# JTAG-USB-POWER.net
KiCad netlist of a schematic drawn in Altium Designer
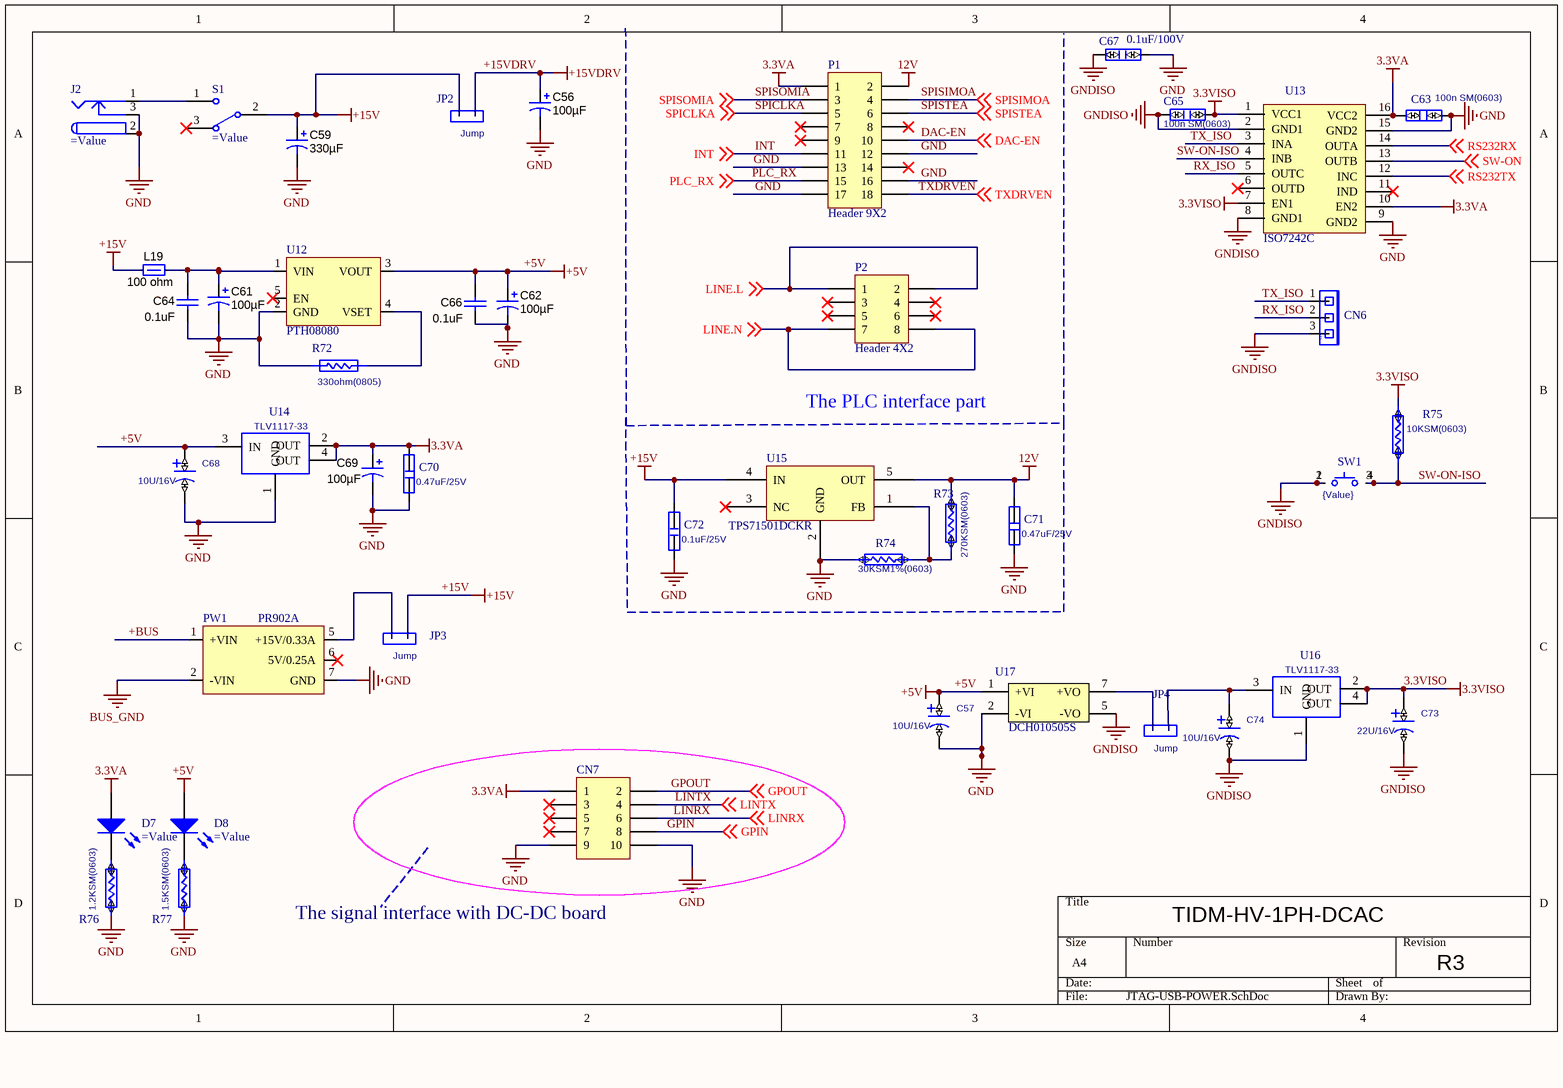
[diagram p0: JTAG-USB-POWER.SchDoc]

(export (version "E")
  (design (tool "Eeschema 10.0.6"))
  (components
    (comp (ref "C56")
      (value "EMVA500ADA101MHA0G")
      (footprint "CAPSMT_62_HA0")
      (description "CAP, AL, 100uF, 50V, +/-20%,  ohm, SMD")
      (fields
        (field (name "VALUEDISPLAYED") "100µF")
        (field (name "MANUFACTURER") "Nippon Chemi-Con")
        (field (name "PUBLISHER") "Texas Instruments")
      )
      (libsource (lib "Capacitor_Aluminum") (part "EMVA500ADA101MHA0G"))
    )
    (comp (ref "C57")
      (value "10U/16V")
      (footprint "CAP-3528")
      (description "CE5080R")
      (libsource (lib "AD-DIPWIN") (part "CE5080R"))
    )
    (comp (ref "C59")
      (value "2R5SVPE330M")
      (footprint "CAPSMT_62_HA0")
      (description "CAP, AL, 330uF, 2.5V, +/-20%, 0.015 ohm, SMD")
      (fields
        (field (name "MANUFACTURER") "Sanyo")
        (field (name "VALUEDISPLAYED") "330µF")
        (field (name "PUBLISHER") "Texas Instruments")
      )
      (libsource (lib "Pass12") (part "2R5SVPE330M"))
    )
    (comp (ref "C61")
      (value "EMVA500ADA101MHA0G")
      (footprint "CAPSMT_62_HA0")
      (description "CAP, AL, 100uF, 50V, +/-20%,  ohm, SMD")
      (fields
        (field (name "VALUEDISPLAYED") "100µF")
        (field (name "MANUFACTURER") "Nippon Chemi-Con")
        (field (name "PUBLISHER") "Texas Instruments")
      )
      (libsource (lib "Capacitor_Aluminum") (part "EMVA500ADA101MHA0G"))
    )
    (comp (ref "C62")
      (value "EMVA500ADA101MHA0G")
      (footprint "CAPSMT_62_HA0")
      (description "CAP, AL, 100uF, 50V, +/-20%,  ohm, SMD")
      (fields
        (field (name "VALUEDISPLAYED") "100µF")
        (field (name "MANUFACTURER") "Nippon Chemi-Con")
        (field (name "PUBLISHER") "Texas Instruments")
      )
      (libsource (lib "Capacitor_Aluminum") (part "EMVA500ADA101MHA0G"))
    )
    (comp (ref "C63")
      (value "100n SM(0603)")
      (footprint "C0603SM")
      (description "C0603SM")
      (libsource (lib "AD-SMDWIN") (part "C0603SM"))
    )
    (comp (ref "C64")
      (value "0.1uF")
      (footprint "0805")
      (description "CAP, CERM, xxxF, xxV, [TempCo], xx%, [PackageReference]")
      (fields
        (field (name "MANUFACTURER") "Used in BOM report")
        (field (name "PUBLISHER") "Texas Instruments")
      )
      (libsource (lib "MiscParts") (part "Capacitor"))
    )
    (comp (ref "C65")
      (value "100n SM(0603)")
      (footprint "C0603SM")
      (description "C0603SM")
      (libsource (lib "AD-SMDWIN") (part "C0603SM"))
    )
    (comp (ref "C66")
      (value "0.1uF")
      (footprint "0805")
      (description "CAP, CERM, xxxF, xxV, [TempCo], xx%, [PackageReference]")
      (fields
        (field (name "MANUFACTURER") "Used in BOM report")
        (field (name "PUBLISHER") "Texas Instruments")
      )
      (libsource (lib "MiscParts") (part "Capacitor"))
    )
    (comp (ref "C67")
      (value "0.1uF/100V")
      (footprint "C/7.5/3/7.5/R3")
      (description "C0603SM")
      (libsource (lib "AD-SMDWIN") (part "C0603SM"))
    )
    (comp (ref "C68")
      (value "10U/16V")
      (footprint "CAP-3528")
      (description "CE5080R")
      (libsource (lib "AD-DIPWIN") (part "CE5080R"))
    )
    (comp (ref "C69")
      (value "EMVA500ADA101MHA0G")
      (footprint "CAPSMT_62_HA0")
      (description "CAP, AL, 100uF, 50V, +/-20%,  ohm, SMD")
      (fields
        (field (name "VALUEDISPLAYED") "100µF")
        (field (name "MANUFACTURER") "Nippon Chemi-Con")
        (field (name "PUBLISHER") "Texas Instruments")
      )
      (libsource (lib "Capacitor_Aluminum") (part "EMVA500ADA101MHA0G"))
    )
    (comp (ref "C70")
      (value "0.47uF/25V")
      (footprint "C0603SM")
      (description "C0805BSM")
      (libsource (lib "AD-SMDWIN") (part "C0805BSM"))
    )
    (comp (ref "C71")
      (value "0.47uF/25V")
      (footprint "C0603SM")
      (description "C0805BSM")
      (libsource (lib "AD-SMDWIN") (part "C0805BSM"))
    )
    (comp (ref "C72")
      (value "0.1uF/25V")
      (footprint "C0603SM")
      (description "C0805BSM")
      (libsource (lib "AD-SMDWIN") (part "C0805BSM"))
    )
    (comp (ref "C73")
      (value "22U/16V")
      (footprint "CAP-3528")
      (description "CE5080R")
      (libsource (lib "AD-DIPWIN") (part "CE5080R"))
    )
    (comp (ref "C74")
      (value "10U/16V")
      (footprint "CAP-3528")
      (description "CE5080R")
      (libsource (lib "AD-DIPWIN") (part "CE5080R"))
    )
    (comp (ref "CN6")
      (value "SCI_PORT")
      (footprint "HDR1X3")
      (description "DB01P03")
      (libsource (lib "AD-DIPWIN") (part "DB01P03"))
    )
    (comp (ref "CN7")
      (value "~")
      (footprint "HDR2X5")
      (description "Header, 5-Pin, Dual row")
      (fields (field (name "PUBLISHER") "Altium Limited"))
      (libsource (lib "Miscellaneous Connectors") (part "Header 5X2"))
    )
    (comp (ref "D7")
      (value "~")
      (footprint "LED0805")
      (description "Typical INFRARED GaAs LED")
      (fields (field (name "PUBLISHER") "Altium Limited"))
      (libsource (lib "Miscellaneous Devices") (part "LED0"))
    )
    (comp (ref "D8")
      (value "~")
      (footprint "LED0805")
      (description "Typical INFRARED GaAs LED")
      (fields (field (name "PUBLISHER") "Altium Limited"))
      (libsource (lib "Miscellaneous Devices") (part "LED0"))
    )
    (comp (ref "J2")
      (value "~")
      (footprint "DCJACK")
      (description "Low Voltage Power Supply Connector")
      (fields (field (name "PUBLISHER") "Altium Limited"))
      (libsource (lib "Miscellaneous Connectors") (part "PWR2.5"))
    )
    (comp (ref "JP2")
      (value "Jump")
      (footprint "HDR1X2")
      (description "J7")
      (libsource (lib "AD-DIPWIN") (part "J7"))
    )
    (comp (ref "JP3")
      (value "Jump")
      (footprint "HDR1X2")
      (description "J7")
      (libsource (lib "AD-DIPWIN") (part "J7"))
    )
    (comp (ref "JP4")
      (value "Jump")
      (footprint "HDR1X2")
      (description "J7")
      (libsource (lib "AD-DIPWIN") (part "J7"))
    )
    (comp (ref "L19")
      (value "100 ohm")
      (footprint "1206")
      (description "Ferrite Bead, 100 ohm @ 100MHz, 3A, 1206")
      (fields
        (field (name "PARTNUMBER") "HI1206N101R-10")
        (field (name "MANUFACTURER") "Laird-Signal Integrity Products")
        (field (name "PUBLISHER") "Texas Instruments")
      )
      (libsource (lib "FerriteBead") (part "HI1206N101R-10"))
    )
    (comp (ref "P1")
      (value "Header 9X2")
      (footprint "HDR2X9")
      (description "Header, 9-Pin, Dual row")
      (fields (field (name "PUBLISHER") "Altium Limited"))
      (libsource (lib "Miscellaneous Connectors") (part "Header 9X2"))
    )
    (comp (ref "P2")
      (value "Header 4X2")
      (footprint "HDR2X4")
      (description "Header, 4-Pin, Dual row")
      (fields (field (name "PUBLISHER") "Altium Limited"))
      (libsource (lib "Miscellaneous Connectors") (part "Header 4X2"))
    )
    (comp (ref "PW1")
      (value "~")
      (footprint "PR902A")
      (fields (field (name "ALTIUM_UNNAMED_1") "PR902A"))
      (libsource (lib "Schlib1") (part "PR902A"))
    )
    (comp (ref "R72")
      (value "330ohm(0805)")
      (footprint "R0805BSM")
      (description "R0805BSM")
      (libsource (lib "AD-SMDWIN") (part "R0805BSM"))
    )
    (comp (ref "R73")
      (value "270KSM(0603)")
      (footprint "R0603SM")
      (description "R0603SM")
      (libsource (lib "AD-SMDWIN") (part "R0603SM"))
    )
    (comp (ref "R74")
      (value "30KSM1%(0603)")
      (footprint "R0603SM")
      (description "R0603SM")
      (libsource (lib "AD-SMDWIN") (part "R0603SM"))
    )
    (comp (ref "R75")
      (value "10KSM(0603)")
      (footprint "R0603SM")
      (description "R0603SM")
      (libsource (lib "AD-SMDWIN") (part "R0603SM"))
    )
    (comp (ref "R76")
      (value "1.2KSM(0603)")
      (footprint "R0603SM")
      (description "R0603SM")
      (libsource (lib "AD-SMDWIN") (part "R0603SM"))
    )
    (comp (ref "R77")
      (value "1.5KSM(0603)")
      (footprint "R0603SM")
      (description "R0603SM")
      (libsource (lib "AD-SMDWIN") (part "R0603SM"))
    )
    (comp (ref "S1")
      (value "~")
      (footprint "SW-3P8X5")
      (description "SPDT Subminiature Toggle Switch, Right Angle Mounting, Vertical Actuation")
      (fields (field (name "PUBLISHER") "Altium Limited"))
      (libsource (lib "Miscellaneous Devices") (part "SW-SPDT"))
    )
    (comp (ref "SW1")
      (value "{Value}")
      (footprint "KRS640")
      (description "KRS640")
      (libsource (lib "AD-DIPWIN") (part "KRS640"))
    )
    (comp (ref "U12")
      (value "~")
      (footprint "PTH08080")
      (fields (field (name "ALTIUM_UNNAMED_1") "PTH08080"))
      (libsource (lib "SOLAR") (part "Component_1"))
    )
    (comp (ref "U13")
      (value "~")
      (footprint "IC-SOIC16P-1.27DW")
      (description "ISO7242")
      (fields (field (name "ALTIUM_UNNAMED_1") "ISO7242C"))
      (libsource (lib "Rectifier_Board") (part "ISO7242"))
    )
    (comp (ref "U14")
      (value "TLV1117-33")
      (footprint "SOT-223-3P")
      (description "LM1117SM")
      (libsource (lib "SolarInv") (part "LM1117SM"))
    )
    (comp (ref "U15")
      (value "TPS71501DCKR")
      (footprint "SOT5-DCK(SC-70)")
      (fields (field (name "ALTIUM_UNNAMED_1") "TPS71501DCKR"))
      (libsource (lib "TPS715XX") (part "TPS71501DCKR"))
    )
    (comp (ref "U16")
      (value "TLV1117-33")
      (footprint "SOT-223-3P")
      (description "LM1117SM")
      (libsource (lib "SolarInv") (part "LM1117SM"))
    )
    (comp (ref "U17")
      (value "~")
      (footprint "DCH010505")
      (fields (field (name "ALTIUM_UNNAMED_1") "DCH010505S"))
      (libsource (lib "Rectifier_Board") (part "DCH010505S"))
    )
  )
  (nets
    (net (code "1") (name "+5V") (class "Default")
      (node (ref "C57") (pin "1") (pinfunction "1_1") (pintype "bidirectional"))
      (node (ref "C62") (pin "1") (pinfunction "+_1") (pintype "passive"))
      (node (ref "C66") (pin "1") (pinfunction "1_1") (pintype "passive"))
      (node (ref "C68") (pin "1") (pinfunction "1_1") (pintype "bidirectional"))
      (node (ref "D8") (pin "1") (pinfunction "A_1") (pintype "passive"))
      (node (ref "U12") (pin "3") (pinfunction "VOUT_3") (pintype "passive"))
      (node (ref "U14") (pin "3") (pinfunction "IN_3") (pintype "passive"))
      (node (ref "U17") (pin "1") (pinfunction "+VI_1") (pintype "open_emitter"))
    )
    (net (code "2") (name "+15V") (class "Default")
      (node (ref "C59") (pin "1") (pinfunction "+_1") (pintype "passive"))
      (node (ref "C72") (pin "2") (pinfunction "2_2") (pintype "passive"))
      (node (ref "JP2") (pin "1") (pinfunction "1_1") (pintype "bidirectional"))
      (node (ref "JP3") (pin "2") (pinfunction "2_2") (pintype "bidirectional"))
      (node (ref "L19") (pin "1") (pinfunction "1_1") (pintype "passive"))
      (node (ref "S1") (pin "2") (pinfunction "2_2") (pintype "passive"))
      (node (ref "U15") (pin "4") (pinfunction "IN_4") (pintype "passive"))
    )
    (net (code "3") (name "+15VDRV") (class "Default")
      (node (ref "C56") (pin "1") (pinfunction "+_1") (pintype "passive"))
      (node (ref "JP2") (pin "2") (pinfunction "2_2") (pintype "bidirectional"))
    )
    (net (code "4") (name "/+BUS") (class "Default")
      (node (ref "PW1") (pin "1") (pinfunction "+VIN_1") (pintype "passive"))
    )
    (net (code "5") (name "/RX_ISO") (class "Default")
      (node (ref "CN6") (pin "2") (pintype "passive"))
      (node (ref "U13") (pin "5") (pinfunction "OUTC_5") (pintype "passive"))
    )
    (net (code "6") (name "/SW-ON-ISO") (class "Default")
      (node (ref "R75") (pin "2") (pinfunction "2_2") (pintype "bidirectional"))
      (node (ref "SW1") (pin "3") (pinfunction "3_3") (pintype "passive"))
      (node (ref "SW1") (pin "4") (pinfunction "4_4") (pintype "passive"))
      (node (ref "U13") (pin "4") (pinfunction "INB_4") (pintype "passive"))
    )
    (net (code "7") (name "/TX_ISO") (class "Default")
      (node (ref "CN6") (pin "1") (pintype "passive"))
      (node (ref "U13") (pin "3") (pinfunction "INA_3") (pintype "passive"))
    )
    (net (code "8") (name "3.3VA") (class "Default")
      (node (ref "C63") (pin "2") (pinfunction "2_2") (pintype "bidirectional"))
      (node (ref "C69") (pin "1") (pinfunction "+_1") (pintype "passive"))
      (node (ref "C70") (pin "2") (pinfunction "2_2") (pintype "passive"))
      (node (ref "CN7") (pin "1") (pinfunction "1_1") (pintype "passive"))
      (node (ref "D7") (pin "1") (pinfunction "A_1") (pintype "passive"))
      (node (ref "P1") (pin "1") (pinfunction "1_1") (pintype "passive"))
      (node (ref "U13") (pin "10") (pinfunction "EN2_10") (pintype "passive"))
      (node (ref "U13") (pin "16") (pinfunction "VCC2_16") (pintype "passive"))
      (node (ref "U14") (pin "2") (pinfunction "OUT_2") (pintype "passive"))
      (node (ref "U14") (pin "4") (pinfunction "OUT_4") (pintype "passive"))
    )
    (net (code "9") (name "3.3VISO") (class "Default")
      (node (ref "C65") (pin "1") (pinfunction "1_1") (pintype "bidirectional"))
      (node (ref "C73") (pin "1") (pinfunction "1_1") (pintype "bidirectional"))
      (node (ref "R75") (pin "1") (pinfunction "1_1") (pintype "bidirectional"))
      (node (ref "U13") (pin "1") (pinfunction "VCC1_1") (pintype "passive"))
      (node (ref "U13") (pin "7") (pinfunction "EN1_7") (pintype "passive"))
      (node (ref "U16") (pin "2") (pinfunction "OUT_2") (pintype "passive"))
      (node (ref "U16") (pin "4") (pinfunction "OUT_4") (pintype "passive"))
    )
    (net (code "10") (name "12V") (class "Default")
      (node (ref "C71") (pin "2") (pinfunction "2_2") (pintype "passive"))
      (node (ref "P1") (pin "2") (pinfunction "2_2") (pintype "passive"))
      (node (ref "R73") (pin "1") (pinfunction "1_1") (pintype "bidirectional"))
      (node (ref "U15") (pin "5") (pinfunction "OUT_5") (pintype "passive"))
    )
    (net (code "11") (name "BUS_GND") (class "Default")
      (node (ref "PW1") (pin "2") (pinfunction "-VIN_2") (pintype "passive"))
    )
    (net (code "12") (name "DAC-EN") (class "Default")
      (node (ref "P1") (pin "10") (pinfunction "10_10") (pintype "passive"))
    )
    (net (code "13") (name "GND") (class "Default")
      (node (ref "C56") (pin "2") (pinfunction "-_2") (pintype "passive"))
      (node (ref "C57") (pin "2") (pinfunction "2_2") (pintype "bidirectional"))
      (node (ref "C59") (pin "2") (pinfunction "-_2") (pintype "passive"))
      (node (ref "C61") (pin "2") (pinfunction "-_2") (pintype "passive"))
      (node (ref "C62") (pin "2") (pinfunction "-_2") (pintype "passive"))
      (node (ref "C63") (pin "1") (pinfunction "1_1") (pintype "bidirectional"))
      (node (ref "C64") (pin "2") (pinfunction "2_2") (pintype "passive"))
      (node (ref "C66") (pin "2") (pinfunction "2_2") (pintype "passive"))
      (node (ref "C67") (pin "1") (pinfunction "1_1") (pintype "bidirectional"))
      (node (ref "C68") (pin "2") (pinfunction "2_2") (pintype "bidirectional"))
      (node (ref "C69") (pin "2") (pinfunction "-_2") (pintype "passive"))
      (node (ref "C70") (pin "1") (pinfunction "1_1") (pintype "passive"))
      (node (ref "C71") (pin "1") (pinfunction "1_1") (pintype "passive"))
      (node (ref "C72") (pin "1") (pinfunction "1_1") (pintype "passive"))
      (node (ref "CN7") (pin "10") (pinfunction "10_10") (pintype "passive"))
      (node (ref "CN7") (pin "9") (pinfunction "9_9") (pintype "passive"))
      (node (ref "J2") (pin "2") (pinfunction "2_2") (pintype "power_in"))
      (node (ref "J2") (pin "3") (pinfunction "3_3") (pintype "power_in"))
      (node (ref "P1") (pin "12") (pinfunction "12_12") (pintype "passive"))
      (node (ref "P1") (pin "13") (pinfunction "13_13") (pintype "passive"))
      (node (ref "P1") (pin "16") (pinfunction "16_16") (pintype "passive"))
      (node (ref "P1") (pin "17") (pinfunction "17_17") (pintype "passive"))
      (node (ref "PW1") (pin "7") (pinfunction "GND_7") (pintype "passive"))
      (node (ref "R72") (pin "1") (pinfunction "1_1") (pintype "passive"))
      (node (ref "R74") (pin "1") (pinfunction "1_1") (pintype "bidirectional"))
      (node (ref "R76") (pin "2") (pinfunction "2_2") (pintype "bidirectional"))
      (node (ref "R77") (pin "2") (pinfunction "2_2") (pintype "bidirectional"))
      (node (ref "U12") (pin "2") (pinfunction "GND_2") (pintype "passive"))
      (node (ref "U13") (pin "15") (pinfunction "GND2_15") (pintype "passive"))
      (node (ref "U13") (pin "9") (pinfunction "GND2_9") (pintype "passive"))
      (node (ref "U14") (pin "1") (pinfunction "GND_1") (pintype "passive"))
      (node (ref "U15") (pin "2") (pinfunction "GND_2") (pintype "passive"))
      (node (ref "U17") (pin "2") (pinfunction "-VI_2") (pintype "open_emitter"))
    )
    (net (code "14") (name "GNDISO") (class "Default")
      (node (ref "C65") (pin "2") (pinfunction "2_2") (pintype "bidirectional"))
      (node (ref "C67") (pin "2") (pinfunction "2_2") (pintype "bidirectional"))
      (node (ref "C73") (pin "2") (pinfunction "2_2") (pintype "bidirectional"))
      (node (ref "C74") (pin "2") (pinfunction "2_2") (pintype "bidirectional"))
      (node (ref "CN6") (pin "3") (pintype "passive"))
      (node (ref "SW1") (pin "1") (pinfunction "1_1") (pintype "passive"))
      (node (ref "SW1") (pin "2") (pinfunction "2_2") (pintype "passive"))
      (node (ref "U13") (pin "2") (pinfunction "GND1_2") (pintype "passive"))
      (node (ref "U13") (pin "8") (pinfunction "GND1_8") (pintype "passive"))
      (node (ref "U16") (pin "1") (pinfunction "GND_1") (pintype "passive"))
      (node (ref "U17") (pin "5") (pinfunction "-VO_5") (pintype "open_emitter"))
    )
    (net (code "15") (name "GPIN") (class "Default")
      (node (ref "CN7") (pin "8") (pinfunction "8_8") (pintype "passive"))
    )
    (net (code "16") (name "GPOUT") (class "Default")
      (node (ref "CN7") (pin "2") (pinfunction "2_2") (pintype "passive"))
    )
    (net (code "17") (name "INT") (class "Default")
      (node (ref "P1") (pin "11") (pinfunction "11_11") (pintype "passive"))
    )
    (net (code "18") (name "LINE.L") (class "Default")
      (node (ref "P2") (pin "1") (pinfunction "1_1") (pintype "passive"))
      (node (ref "P2") (pin "2") (pinfunction "2_2") (pintype "passive"))
    )
    (net (code "19") (name "LINE.N") (class "Default")
      (node (ref "P2") (pin "7") (pinfunction "7_7") (pintype "passive"))
      (node (ref "P2") (pin "8") (pinfunction "8_8") (pintype "passive"))
    )
    (net (code "20") (name "LINRX") (class "Default")
      (node (ref "CN7") (pin "6") (pinfunction "6_6") (pintype "passive"))
    )
    (net (code "21") (name "LINTX") (class "Default")
      (node (ref "CN7") (pin "4") (pinfunction "4_4") (pintype "passive"))
    )
    (net (code "22") (name "Net-(C61-+)") (class "Default")
      (node (ref "C61") (pin "1") (pinfunction "+_1") (pintype "passive"))
      (node (ref "C64") (pin "1") (pinfunction "1_1") (pintype "passive"))
      (node (ref "L19") (pin "2") (pinfunction "2_2") (pintype "passive"))
      (node (ref "U12") (pin "1") (pinfunction "VIN_1") (pintype "passive"))
    )
    (net (code "23") (name "Net-(D7-K)") (class "Default")
      (node (ref "D7") (pin "2") (pinfunction "K_2") (pintype "passive"))
      (node (ref "R76") (pin "1") (pinfunction "1_1") (pintype "bidirectional"))
    )
    (net (code "24") (name "Net-(D8-K)") (class "Default")
      (node (ref "D8") (pin "2") (pinfunction "K_2") (pintype "passive"))
      (node (ref "R77") (pin "1") (pinfunction "1_1") (pintype "bidirectional"))
    )
    (net (code "25") (name "Net-(J2-Pad1)") (class "Default")
      (node (ref "J2") (pin "1") (pinfunction "1_1") (pintype "power_in"))
      (node (ref "S1") (pin "1") (pinfunction "1_1") (pintype "passive"))
    )
    (net (code "26") (name "Net-(PW1-+15V{slash}0.33A)") (class "Default")
      (node (ref "JP3") (pin "1") (pinfunction "1_1") (pintype "bidirectional"))
      (node (ref "PW1") (pin "5") (pinfunction "+15V/0.33A_5") (pintype "passive"))
    )
    (net (code "27") (name "Net-(U12-VSET)") (class "Default")
      (node (ref "R72") (pin "2") (pinfunction "2_2") (pintype "passive"))
      (node (ref "U12") (pin "4") (pinfunction "VSET_4") (pintype "passive"))
    )
    (net (code "28") (name "Net-(U15-FB)") (class "Default")
      (node (ref "R73") (pin "2") (pinfunction "2_2") (pintype "bidirectional"))
      (node (ref "R74") (pin "2") (pinfunction "2_2") (pintype "bidirectional"))
      (node (ref "U15") (pin "1") (pinfunction "FB_1") (pintype "passive"))
    )
    (net (code "29") (name "Net-(U16-IN)") (class "Default")
      (node (ref "C74") (pin "1") (pinfunction "1_1") (pintype "bidirectional"))
      (node (ref "JP4") (pin "2") (pinfunction "2_2") (pintype "bidirectional"))
      (node (ref "U16") (pin "3") (pinfunction "IN_3") (pintype "passive"))
    )
    (net (code "30") (name "Net-(U17-+VO)") (class "Default")
      (node (ref "JP4") (pin "1") (pinfunction "1_1") (pintype "bidirectional"))
      (node (ref "U17") (pin "7") (pinfunction "+VO_7") (pintype "open_emitter"))
    )
    (net (code "31") (name "PLC_RX") (class "Default")
      (node (ref "P1") (pin "15") (pinfunction "15_15") (pintype "passive"))
    )
    (net (code "32") (name "RS232RX") (class "Default")
      (node (ref "U13") (pin "14") (pinfunction "OUTA_14") (pintype "passive"))
    )
    (net (code "33") (name "RS232TX") (class "Default")
      (node (ref "U13") (pin "12") (pinfunction "INC_12") (pintype "passive"))
    )
    (net (code "34") (name "SPICLKA") (class "Default")
      (node (ref "P1") (pin "5") (pinfunction "5_5") (pintype "passive"))
    )
    (net (code "35") (name "SPISIMOA") (class "Default")
      (node (ref "P1") (pin "4") (pinfunction "4_4") (pintype "passive"))
    )
    (net (code "36") (name "SPISOMIA") (class "Default")
      (node (ref "P1") (pin "3") (pinfunction "3_3") (pintype "passive"))
    )
    (net (code "37") (name "SPISTEA") (class "Default")
      (node (ref "P1") (pin "6") (pinfunction "6_6") (pintype "passive"))
    )
    (net (code "38") (name "SW-ON") (class "Default")
      (node (ref "U13") (pin "13") (pinfunction "OUTB_13") (pintype "passive"))
    )
    (net (code "39") (name "TXDRVEN") (class "Default")
      (node (ref "P1") (pin "18") (pinfunction "18_18") (pintype "passive"))
    )
    (net (code "40") (name "unconnected-(CN7-Pad3)") (class "Default")
      (node (ref "CN7") (pin "3") (pinfunction "3_3") (pintype "passive+no_connect"))
    )
    (net (code "41") (name "unconnected-(CN7-Pad5)") (class "Default")
      (node (ref "CN7") (pin "5") (pinfunction "5_5") (pintype "passive+no_connect"))
    )
    (net (code "42") (name "unconnected-(CN7-Pad7)") (class "Default")
      (node (ref "CN7") (pin "7") (pinfunction "7_7") (pintype "passive+no_connect"))
    )
    (net (code "43") (name "unconnected-(P1-Pad7)") (class "Default")
      (node (ref "P1") (pin "7") (pinfunction "7_7") (pintype "passive+no_connect"))
    )
    (net (code "44") (name "unconnected-(P1-Pad8)") (class "Default")
      (node (ref "P1") (pin "8") (pinfunction "8_8") (pintype "passive+no_connect"))
    )
    (net (code "45") (name "unconnected-(P1-Pad9)") (class "Default")
      (node (ref "P1") (pin "9") (pinfunction "9_9") (pintype "passive+no_connect"))
    )
    (net (code "46") (name "unconnected-(P1-Pad14)") (class "Default")
      (node (ref "P1") (pin "14") (pinfunction "14_14") (pintype "passive+no_connect"))
    )
    (net (code "47") (name "unconnected-(P2-Pad3)") (class "Default")
      (node (ref "P2") (pin "3") (pinfunction "3_3") (pintype "passive+no_connect"))
    )
    (net (code "48") (name "unconnected-(P2-Pad4)") (class "Default")
      (node (ref "P2") (pin "4") (pinfunction "4_4") (pintype "passive+no_connect"))
    )
    (net (code "49") (name "unconnected-(P2-Pad5)") (class "Default")
      (node (ref "P2") (pin "5") (pinfunction "5_5") (pintype "passive+no_connect"))
    )
    (net (code "50") (name "unconnected-(P2-Pad6)") (class "Default")
      (node (ref "P2") (pin "6") (pinfunction "6_6") (pintype "passive+no_connect"))
    )
    (net (code "51") (name "unconnected-(PW1-5V{slash}0.25A-Pad6)") (class "Default")
      (node (ref "PW1") (pin "6") (pinfunction "5V/0.25A_6") (pintype "passive+no_connect"))
    )
    (net (code "52") (name "unconnected-(S1-Pad3)") (class "Default")
      (node (ref "S1") (pin "3") (pinfunction "3_3") (pintype "passive+no_connect"))
    )
    (net (code "53") (name "unconnected-(U12-EN-Pad5)") (class "Default")
      (node (ref "U12") (pin "5") (pinfunction "EN_5") (pintype "passive+no_connect"))
    )
    (net (code "54") (name "unconnected-(U13-IND-Pad11)") (class "Default")
      (node (ref "U13") (pin "11") (pinfunction "IND_11") (pintype "passive+no_connect"))
    )
    (net (code "55") (name "unconnected-(U13-OUTD-Pad6)") (class "Default")
      (node (ref "U13") (pin "6") (pinfunction "OUTD_6") (pintype "passive+no_connect"))
    )
    (net (code "56") (name "unconnected-(U15-NC-Pad3)") (class "Default")
      (node (ref "U15") (pin "3") (pinfunction "NC_3") (pintype "passive+no_connect"))
    )
  )
)
